# duel_mems_mic.net
KiCad netlist of a schematic drawn in EAGLE
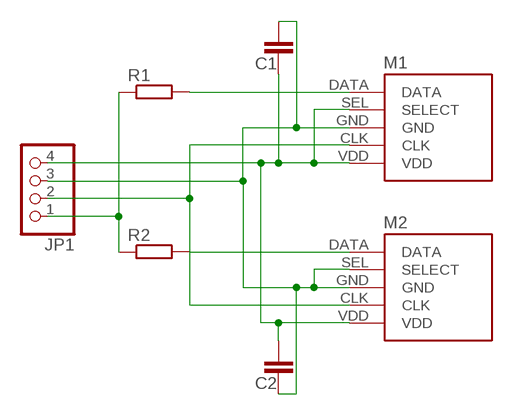
[diagram p0: schematic, sheet 1]

(export (version "E")
  (design (tool "Eeschema 10.0.6"))
  (components
    (comp (ref "C1")
      (value "C-EUC0402")
      (footprint "eagle-import:C0402")
      (libsource (lib "eagle-import") (part "C-EUC0402"))
    )
    (comp (ref "C2")
      (value "C-EUC0402")
      (footprint "eagle-import:C0402")
      (libsource (lib "eagle-import") (part "C-EUC0402"))
    )
    (comp (ref "JP1")
      (value "PINHD-1X4")
      (footprint "eagle-import:1X04")
      (libsource (lib "eagle-import") (part "PINHD-1X4"))
    )
    (comp (ref "M1")
      (value "MEMS_MIC_IM69D130-DS")
      (footprint "eagle-import:IM69D130-DS")
      (libsource (lib "eagle-import") (part "MEMS_MIC_IM69D130-DS"))
    )
    (comp (ref "M2")
      (value "MEMS_MIC_IM69D130-DS")
      (footprint "eagle-import:IM69D130-DS")
      (libsource (lib "eagle-import") (part "MEMS_MIC_IM69D130-DS"))
    )
    (comp (ref "R1")
      (value "R-EU_R0402")
      (footprint "eagle-import:R0402")
      (libsource (lib "eagle-import") (part "R-EU_R0402"))
    )
    (comp (ref "R2")
      (value "R-EU_R0402")
      (footprint "eagle-import:R0402")
      (libsource (lib "eagle-import") (part "R-EU_R0402"))
    )
  )
  (nets
    (net (code "1") (name "Net-(JP1-Pad1)") (class "Default")
      (node (ref "JP1") (pin "1") (pinfunction "1_1") (pintype "passive"))
      (node (ref "R1") (pin "1") (pinfunction "1_1") (pintype "passive"))
      (node (ref "R2") (pin "1") (pinfunction "1_1") (pintype "passive"))
    )
    (net (code "2") (name "Net-(JP1-Pad2)") (class "Default")
      (node (ref "JP1") (pin "2") (pinfunction "2_2") (pintype "passive"))
      (node (ref "M1") (pin "CLK") (pinfunction "CLK_CLK") (pintype "bidirectional"))
      (node (ref "M2") (pin "CLK") (pinfunction "CLK_CLK") (pintype "bidirectional"))
    )
    (net (code "3") (name "Net-(M1-PadDATA)") (class "Default")
      (node (ref "M1") (pin "DATA") (pinfunction "DATA_DATA") (pintype "bidirectional"))
      (node (ref "R1") (pin "2") (pinfunction "2_2") (pintype "passive"))
    )
    (net (code "4") (name "Net-(M1-SELECT)") (class "Default")
      (node (ref "C1") (pin "2") (pinfunction "2_2") (pintype "passive"))
      (node (ref "C2") (pin "1") (pinfunction "1_1") (pintype "passive"))
      (node (ref "JP1") (pin "4") (pinfunction "4_4") (pintype "passive"))
      (node (ref "M1") (pin "SEL") (pinfunction "SELECT_SEL") (pintype "bidirectional"))
      (node (ref "M1") (pin "VDD") (pinfunction "VDD_VDD") (pintype "bidirectional"))
      (node (ref "M2") (pin "VDD") (pinfunction "VDD_VDD") (pintype "bidirectional"))
    )
    (net (code "5") (name "Net-(M2-PadDATA)") (class "Default")
      (node (ref "M2") (pin "DATA") (pinfunction "DATA_DATA") (pintype "bidirectional"))
      (node (ref "R2") (pin "2") (pinfunction "2_2") (pintype "passive"))
    )
    (net (code "6") (name "Net-(M2-SELECT)") (class "Default")
      (node (ref "C1") (pin "1") (pinfunction "1_1") (pintype "passive"))
      (node (ref "C2") (pin "2") (pinfunction "2_2") (pintype "passive"))
      (node (ref "JP1") (pin "3") (pinfunction "3_3") (pintype "passive"))
      (node (ref "M1") (pin "GND") (pinfunction "GND_GND") (pintype "bidirectional"))
      (node (ref "M2") (pin "GND") (pinfunction "GND_GND") (pintype "bidirectional"))
      (node (ref "M2") (pin "SEL") (pinfunction "SELECT_SEL") (pintype "bidirectional"))
    )
  )
)
